# VIVA_PIC16_REV4-5.net
KiCad netlist of a schematic drawn in EAGLE
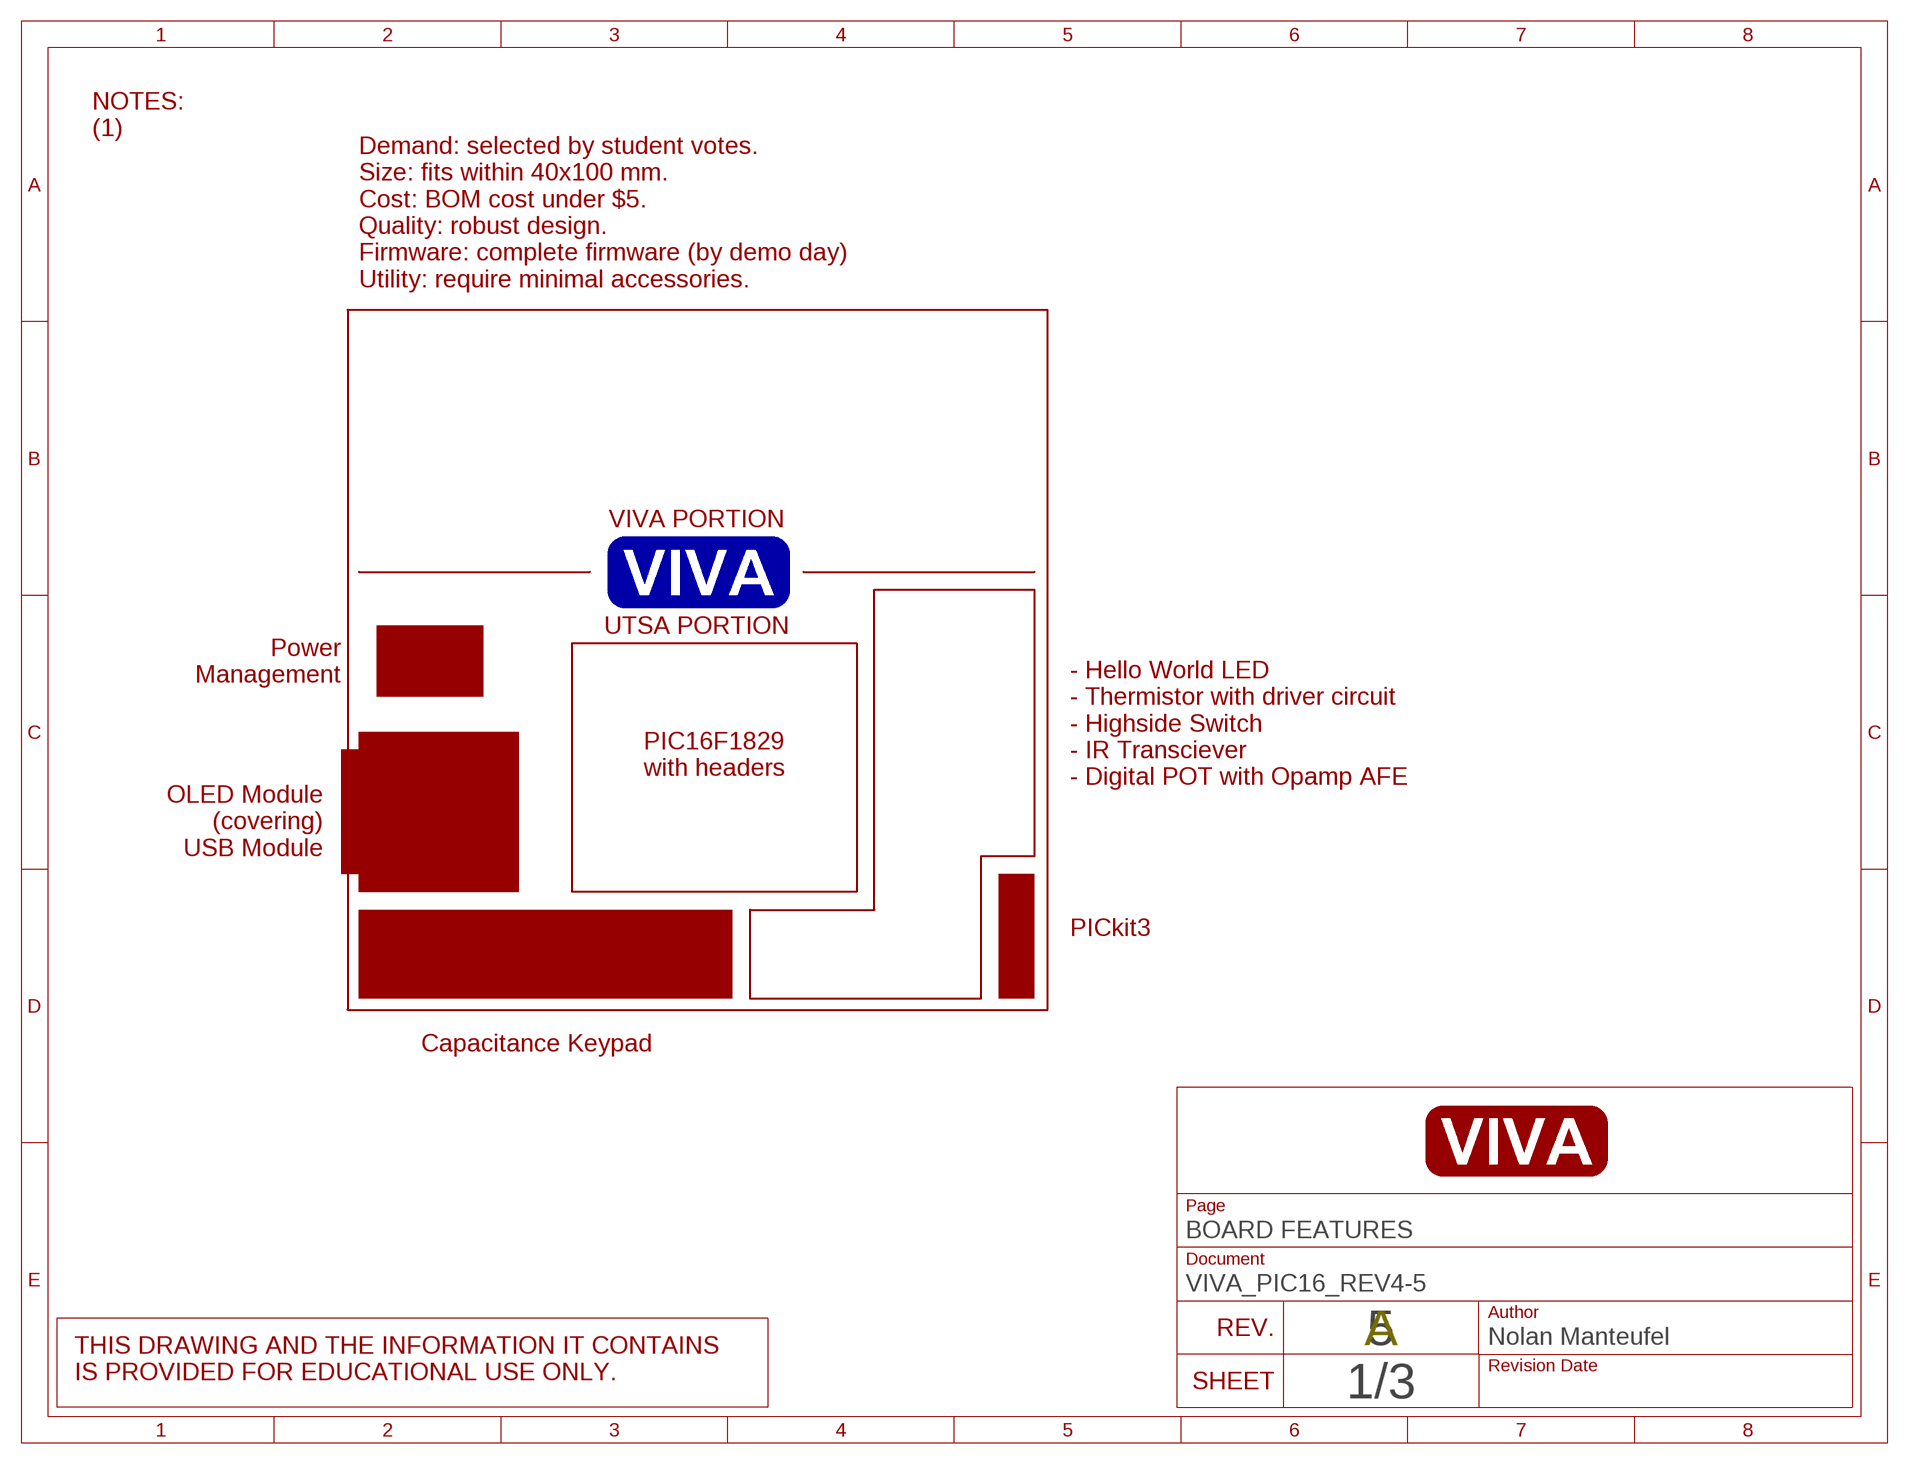
[diagram p0: schematic, sheet 1]
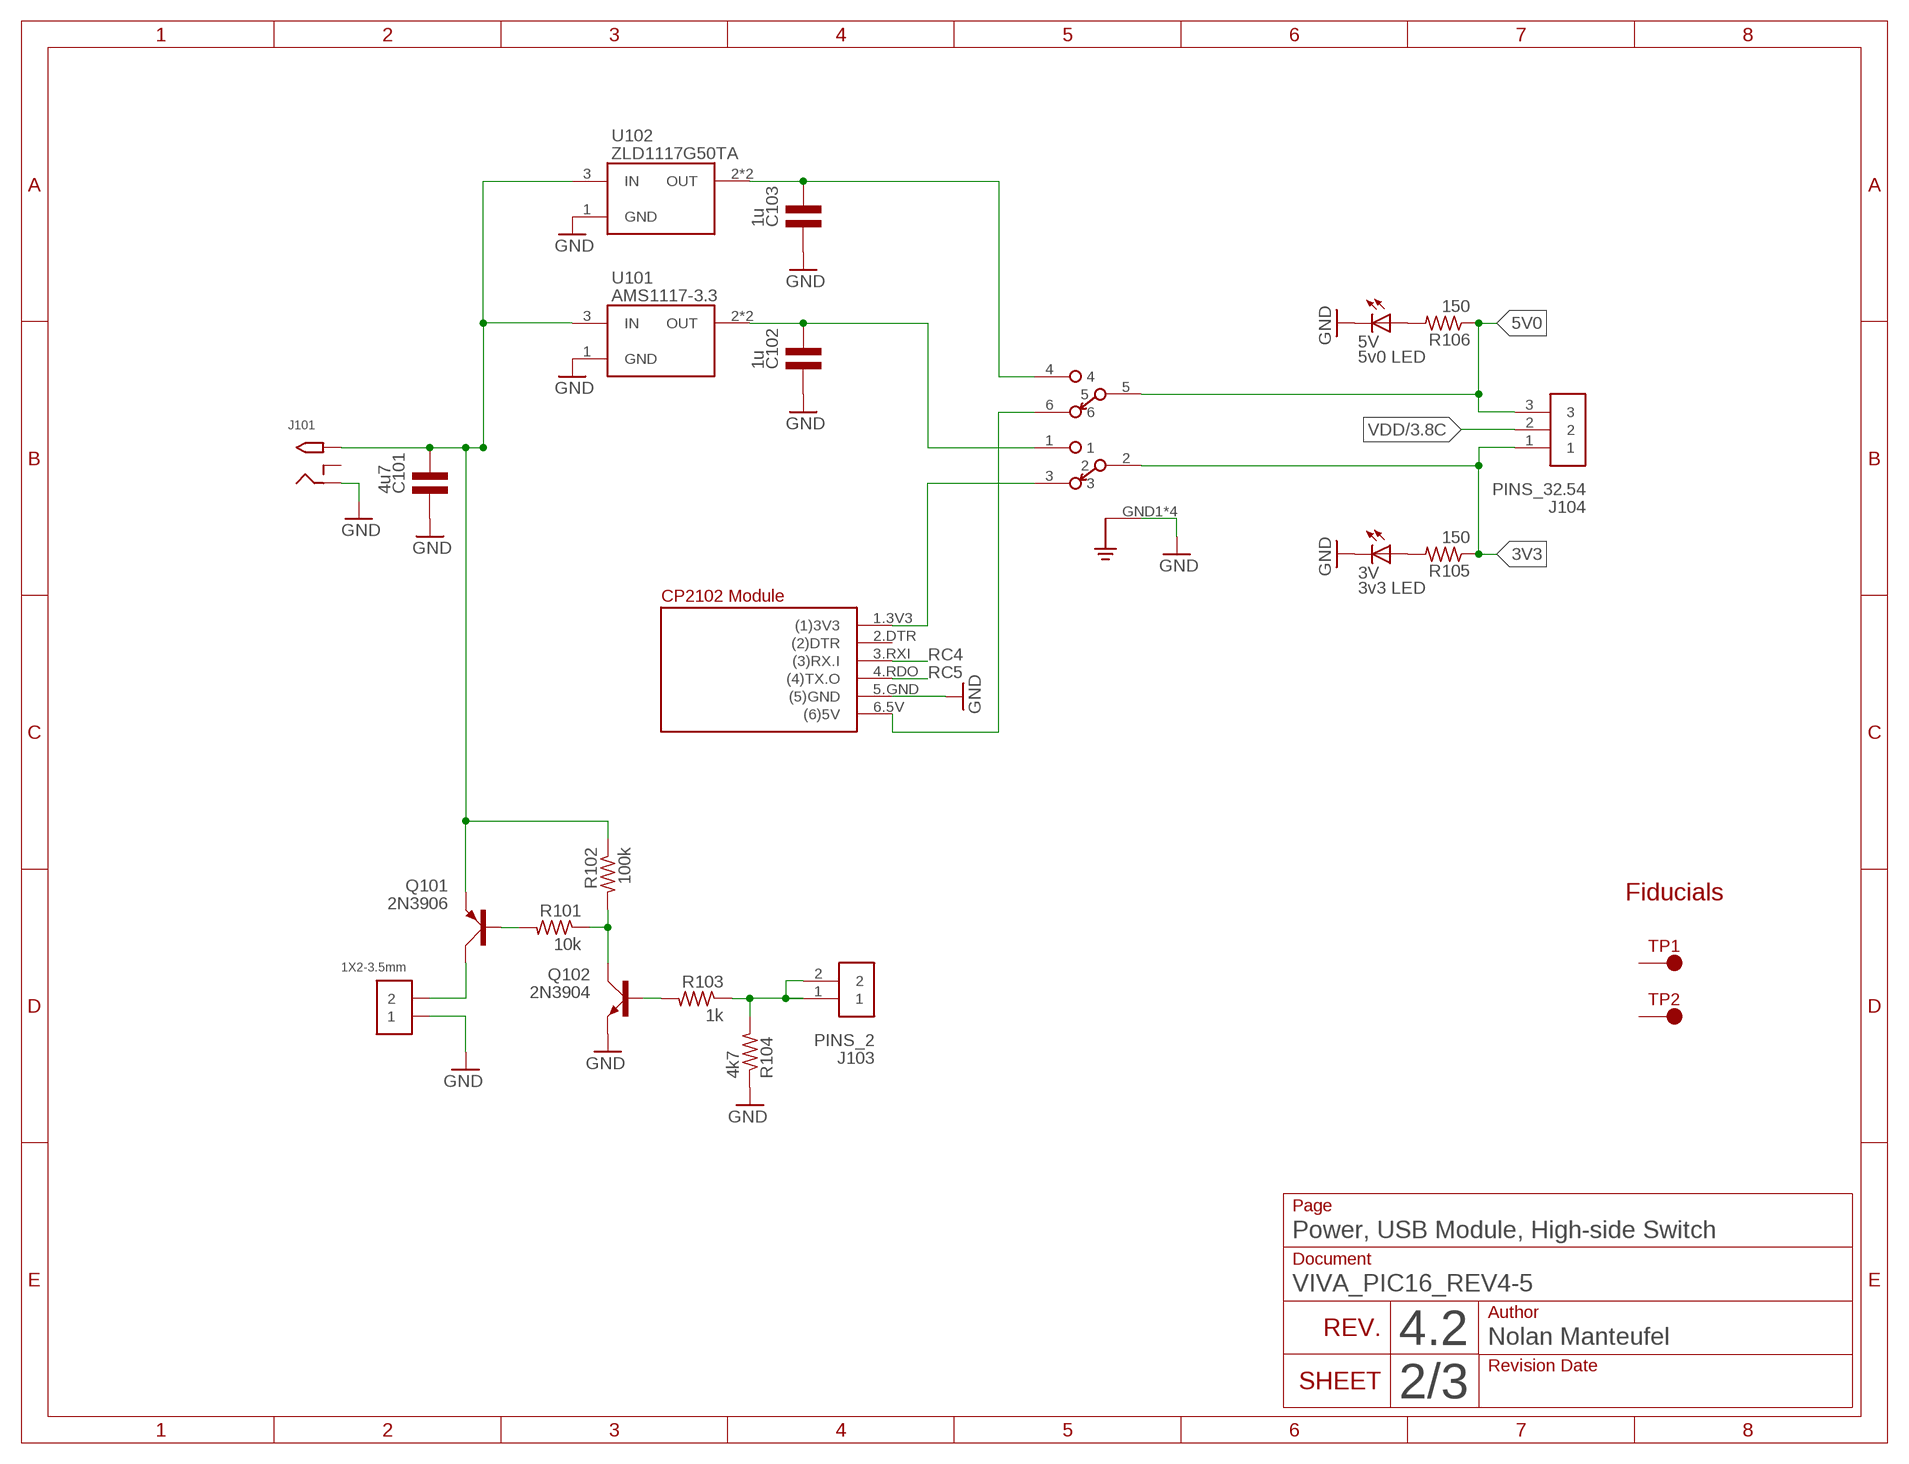
[diagram p1: schematic, sheet 2]
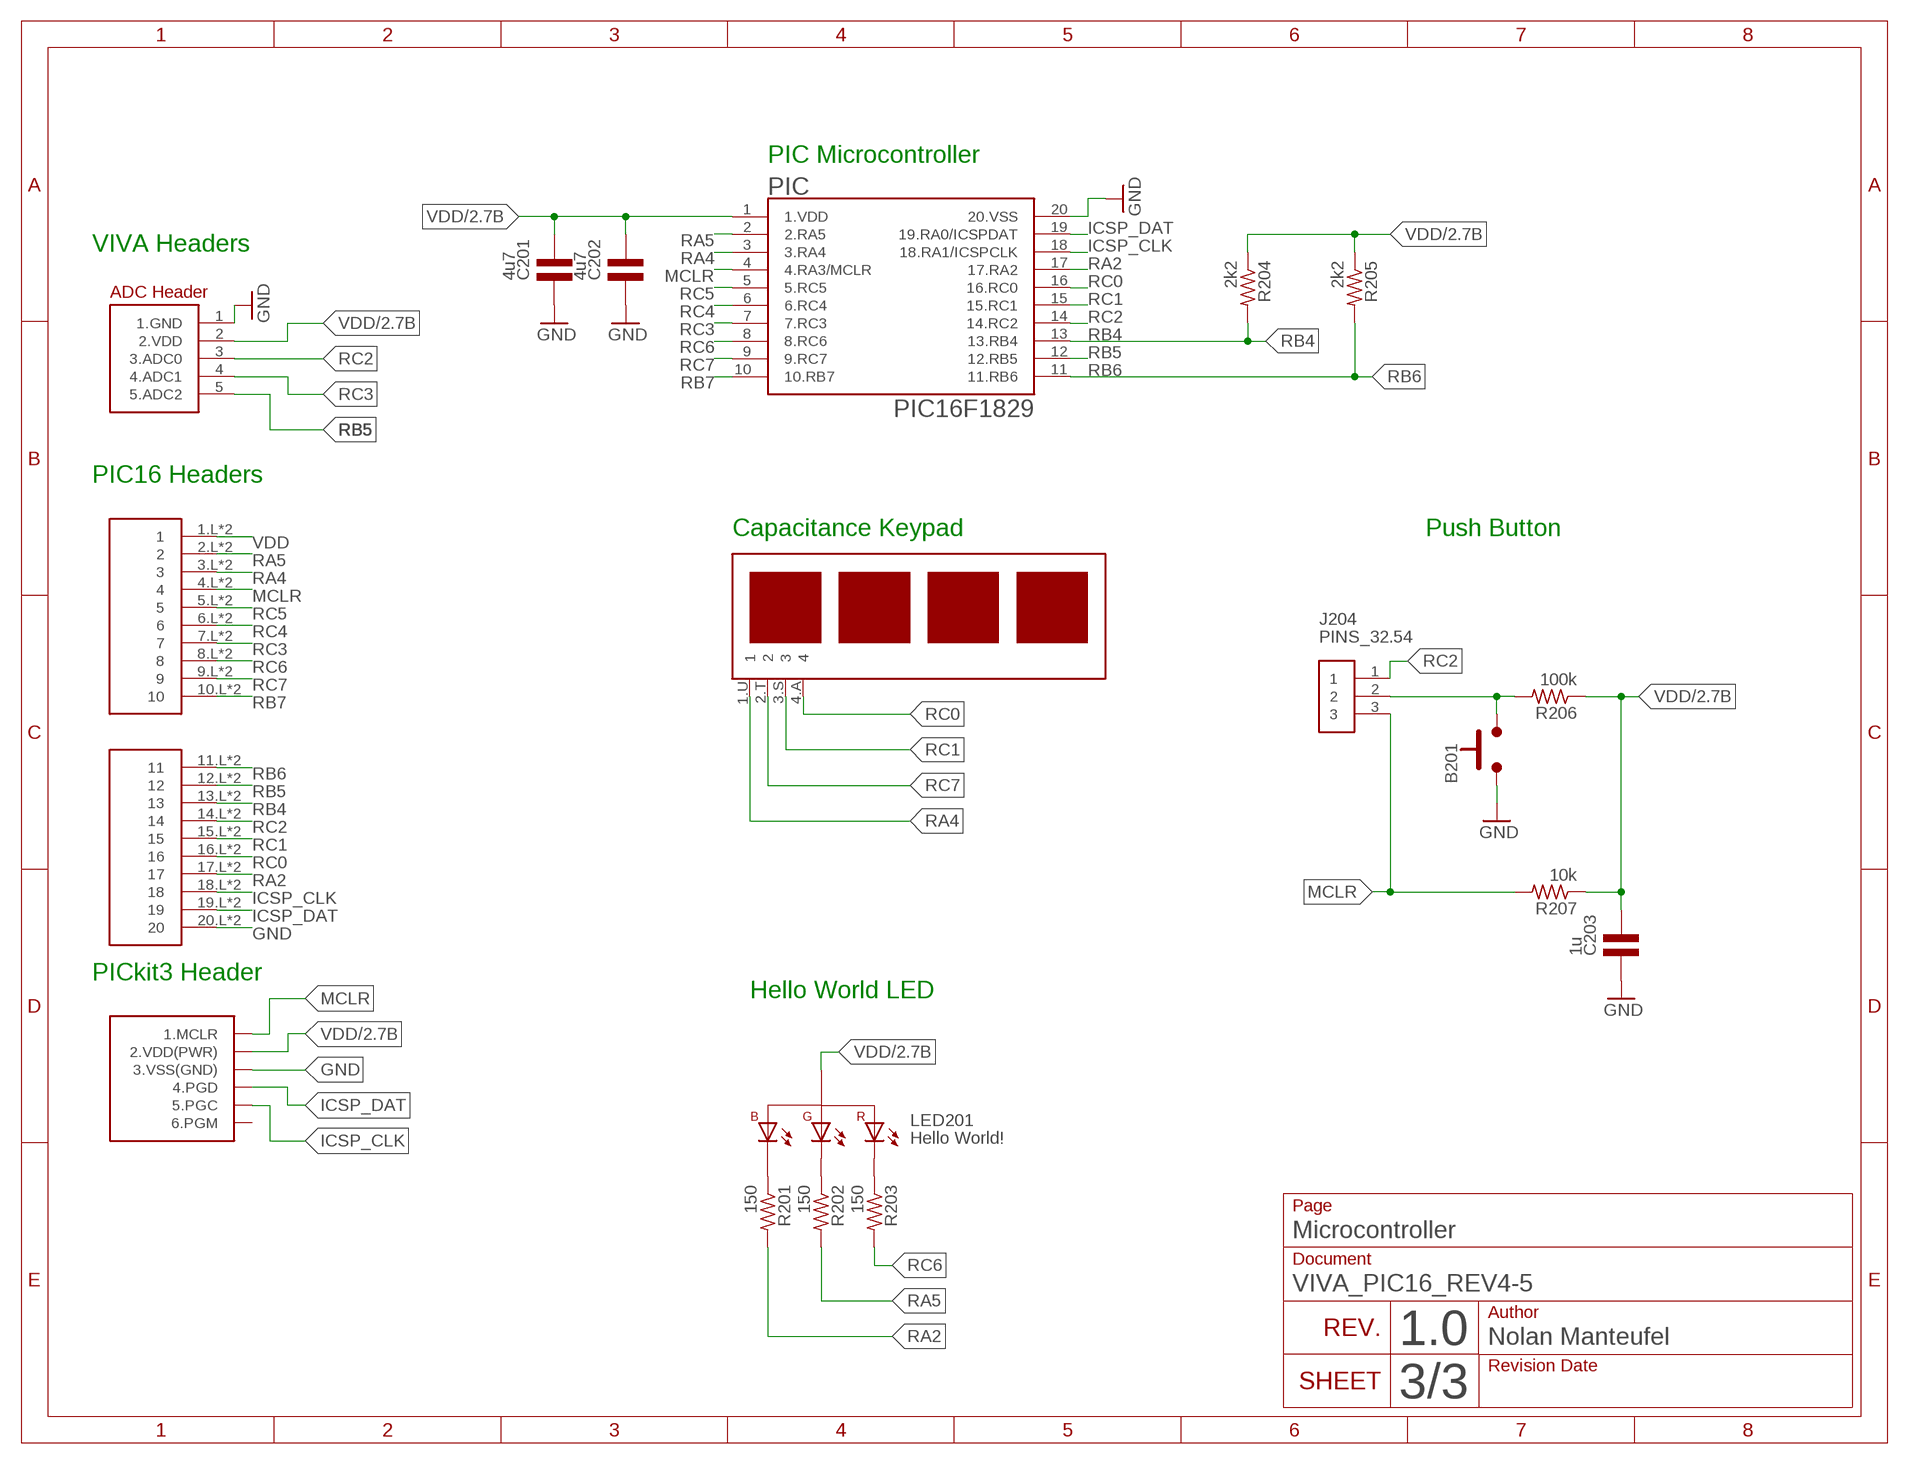
[diagram p2: schematic, sheet 3]

(export (version "E")
  (design (tool "Eeschema 10.0.6"))
  (components
    (comp (ref "B201")
      (value "PUSHBUTTON6X6MM")
      (footprint "eagle-import:6X6MM")
      (libsource (lib "eagle-import") (part "PUSHBUTTON6X6MM"))
    )
    (comp (ref "C201")
      (value "4u7")
      (footprint "eagle-import:C0805")
      (libsource (lib "eagle-import") (part "C0805"))
    )
    (comp (ref "C202")
      (value "4u7")
      (footprint "eagle-import:C0805")
      (libsource (lib "eagle-import") (part "C0805"))
    )
    (comp (ref "C203")
      (value "1u")
      (footprint "eagle-import:C0805")
      (libsource (lib "eagle-import") (part "C0805"))
    )
    (comp (ref "J201")
      (value "VIVA_PIC16")
      (footprint "eagle-import:VIVA_PIC16")
      (libsource (lib "eagle-import") (part "VIVA_PIC16"))
    )
    (comp (ref "J202")
      (value "VIVA-HEADER-ADCNONAME")
      (footprint "eagle-import:VIVA-HEADER-ADC-NONAME")
      (libsource (lib "eagle-import") (part "VIVA-HEADER-ADCNONAME"))
    )
    (comp (ref "J203")
      (value "PICKIT3")
      (footprint "eagle-import:PICKIT3")
      (libsource (lib "eagle-import") (part "PICKIT3"))
    )
    (comp (ref "J204")
      (value "PINS_32.54")
      (footprint "eagle-import:PINS_3")
      (libsource (lib "eagle-import") (part "PINS_32.54"))
    )
    (comp (ref "LED201")
      (value "Hello World!")
      (footprint "eagle-import:LED_RGB-5050")
      (libsource (lib "eagle-import") (part "RGB_LED"))
    )
    (comp (ref "PIC")
      (value "PIC16F1829")
      (footprint "eagle-import:SOP20-NEW")
      (libsource (lib "eagle-import") (part "PIC16F1829"))
    )
    (comp (ref "R201")
      (value "150")
      (footprint "eagle-import:R0805")
      (libsource (lib "eagle-import") (part "R-US_R0805"))
    )
    (comp (ref "R202")
      (value "150")
      (footprint "eagle-import:R0805")
      (libsource (lib "eagle-import") (part "R-US_R0805"))
    )
    (comp (ref "R203")
      (value "150")
      (footprint "eagle-import:R0805")
      (libsource (lib "eagle-import") (part "R-US_R0805"))
    )
    (comp (ref "R204")
      (value "2k2")
      (footprint "eagle-import:R0805")
      (libsource (lib "eagle-import") (part "R-US_R0805"))
    )
    (comp (ref "R205")
      (value "2k2")
      (footprint "eagle-import:R0805")
      (libsource (lib "eagle-import") (part "R-US_R0805"))
    )
    (comp (ref "R206")
      (value "100k")
      (footprint "eagle-import:R0805")
      (libsource (lib "eagle-import") (part "R-US_R0805"))
    )
    (comp (ref "R207")
      (value "10k")
      (footprint "eagle-import:R0805")
      (libsource (lib "eagle-import") (part "R-US_R0805"))
    )
    (comp (ref "U$201")
      (value "VIVA_UTSA-KEYPAD")
      (footprint "eagle-import:VIVA_UTSA-KEYPAD")
      (libsource (lib "eagle-import") (part "VIVA_UTSA-KEYPAD"))
    )
    (comp (ref "3V")
      (value "3v3 LED")
      (footprint "eagle-import:CHIPLED_0805")
      (libsource (lib "eagle-import") (part "LEDCHIPLED_0805"))
    )
    (comp (ref "5V")
      (value "5v0 LED")
      (footprint "eagle-import:CHIPLED_0805")
      (libsource (lib "eagle-import") (part "LEDCHIPLED_0805"))
    )
    (comp (ref "C101")
      (value "4u7")
      (footprint "eagle-import:C0805")
      (libsource (lib "eagle-import") (part "C0805"))
    )
    (comp (ref "C102")
      (value "1u")
      (footprint "eagle-import:C0805")
      (libsource (lib "eagle-import") (part "C0805"))
    )
    (comp (ref "C103")
      (value "1u")
      (footprint "eagle-import:C0805")
      (libsource (lib "eagle-import") (part "C0805"))
    )
    (comp (ref "J101")
      (value "2.1MMJACKTHM")
      (footprint "eagle-import:PJ-102A")
      (libsource (lib "eagle-import") (part "2.1MMJACKTHM"))
    )
    (comp (ref "J102")
      (value "1X2-3.5MM-3.5MM")
      (footprint "eagle-import:1X2-3.5MM")
      (libsource (lib "eagle-import") (part "1X2-3.5MM-3.5MM"))
    )
    (comp (ref "J103")
      (value "PINS_2")
      (footprint "eagle-import:PINS_2")
      (libsource (lib "eagle-import") (part "PINS_2"))
    )
    (comp (ref "J104")
      (value "PINS_32.54")
      (footprint "eagle-import:PINS_3")
      (libsource (lib "eagle-import") (part "PINS_32.54"))
    )
    (comp (ref "M101")
      (value "VIVA_USB-TTL")
      (footprint "eagle-import:VIVA_USB_TTL_SUBTEXT")
      (libsource (lib "eagle-import") (part "VIVA_USB-TTL"))
    )
    (comp (ref "Q101")
      (value "2N3906")
      (footprint "eagle-import:SOT23")
      (libsource (lib "eagle-import") (part "2N3906SOT23"))
    )
    (comp (ref "Q102")
      (value "2N3904")
      (footprint "eagle-import:SOT23")
      (libsource (lib "eagle-import") (part "2N3904SOT23"))
    )
    (comp (ref "R101")
      (value "10k")
      (footprint "eagle-import:R0805")
      (libsource (lib "eagle-import") (part "R-US_R0805"))
    )
    (comp (ref "R102")
      (value "100k")
      (footprint "eagle-import:R0805")
      (libsource (lib "eagle-import") (part "R-US_R0805"))
    )
    (comp (ref "R103")
      (value "1k")
      (footprint "eagle-import:R0805")
      (libsource (lib "eagle-import") (part "R-US_R0805"))
    )
    (comp (ref "R104")
      (value "4k7")
      (footprint "eagle-import:R0805")
      (libsource (lib "eagle-import") (part "R-US_R0805"))
    )
    (comp (ref "R105")
      (value "150")
      (footprint "eagle-import:R0805")
      (libsource (lib "eagle-import") (part "R-US_R0805"))
    )
    (comp (ref "R106")
      (value "150")
      (footprint "eagle-import:R0805")
      (libsource (lib "eagle-import") (part "R-US_R0805"))
    )
    (comp (ref "S101")
      (value "SWITCH_OS202013")
      (footprint "eagle-import:OS202013MT5QN1")
      (libsource (lib "eagle-import") (part "SWITCH_OS202013"))
    )
    (comp (ref "TP1")
      (value "TESTPOINTFIDUCIAL")
      (footprint "eagle-import:FIDUCIAL")
      (libsource (lib "eagle-import") (part "TESTPOINTFIDUCIAL"))
    )
    (comp (ref "TP2")
      (value "TESTPOINTFIDUCIAL")
      (footprint "eagle-import:FIDUCIAL")
      (libsource (lib "eagle-import") (part "TESTPOINTFIDUCIAL"))
    )
    (comp (ref "U101")
      (value "AMS1117-3.3")
      (footprint "eagle-import:SOT223")
      (libsource (lib "eagle-import") (part "REGULATOR_SCHLM1117"))
    )
    (comp (ref "U102")
      (value "ZLD1117G50TA")
      (footprint "eagle-import:SOT223")
      (libsource (lib "eagle-import") (part "REGULATOR_SCHLM1117"))
    )
    (comp (ref "U$1")
      (value "VIVA_LOGO")
      (footprint "eagle-import:VIVA_LOGO")
      (libsource (lib "eagle-import") (part "VIVA_LOGO"))
    )
  )
  (nets
    (net (code "1") (name "3V3") (class "Default")
      (node (ref "J104") (pin "1") (pinfunction "1_1") (pintype "bidirectional"))
      (node (ref "R105") (pin "1") (pinfunction "1_1") (pintype "passive"))
      (node (ref "S101") (pin "2") (pinfunction "2_2") (pintype "bidirectional"))
    )
    (net (code "2") (name "5V0") (class "Default")
      (node (ref "J104") (pin "3") (pinfunction "3_3") (pintype "bidirectional"))
      (node (ref "R106") (pin "1") (pinfunction "1_1") (pintype "passive"))
      (node (ref "S101") (pin "5") (pinfunction "5_5") (pintype "bidirectional"))
    )
    (net (code "3") (name "GND") (class "Default")
      (node (ref "3V") (pin "C") (pinfunction "C_C") (pintype "passive"))
      (node (ref "5V") (pin "C") (pinfunction "C_C") (pintype "passive"))
      (node (ref "B201") (pin "1.A") (pinfunction "1_1.A") (pintype "bidirectional"))
      (node (ref "B201") (pin "2.A") (pinfunction "1_2.A") (pintype "bidirectional"))
      (node (ref "C101") (pin "1") (pinfunction "P$1_1") (pintype "passive"))
      (node (ref "C102") (pin "1") (pinfunction "P$1_1") (pintype "passive"))
      (node (ref "C103") (pin "1") (pinfunction "P$1_1") (pintype "passive"))
      (node (ref "C201") (pin "1") (pinfunction "P$1_1") (pintype "passive"))
      (node (ref "C202") (pin "1") (pinfunction "P$1_1") (pintype "passive"))
      (node (ref "C203") (pin "1") (pinfunction "P$1_1") (pintype "passive"))
      (node (ref "J101") (pin "RING") (pinfunction "RING_RING") (pintype "bidirectional"))
      (node (ref "J102") (pin "1") (pinfunction "1_1") (pintype "passive"))
      (node (ref "J201") (pin "20.L") (pinfunction "20_20.L") (pintype "bidirectional"))
      (node (ref "J201") (pin "20.R") (pinfunction "20_20.R") (pintype "bidirectional"))
      (node (ref "J202") (pin "1") (pinfunction "1.GND_1") (pintype "bidirectional"))
      (node (ref "J203") (pin "3") (pinfunction "3.VSS(GND)_3") (pintype "bidirectional"))
      (node (ref "M101") (pin "5.GND") (pinfunction "(5)GND_5.GND") (pintype "bidirectional"))
      (node (ref "PIC") (pin "20") (pinfunction "20.VSS_20") (pintype "bidirectional"))
      (node (ref "Q102") (pin "2") (pinfunction "E_2") (pintype "passive"))
      (node (ref "R104") (pin "1") (pinfunction "1_1") (pintype "passive"))
      (node (ref "S101") (pin "GND1") (pinfunction "GND_GND1") (pintype "bidirectional"))
      (node (ref "S101") (pin "GND2") (pinfunction "GND_GND2") (pintype "bidirectional"))
      (node (ref "S101") (pin "GND3") (pinfunction "GND_GND3") (pintype "bidirectional"))
      (node (ref "S101") (pin "GND4") (pinfunction "GND_GND4") (pintype "bidirectional"))
      (node (ref "U101") (pin "1") (pinfunction "GND_1") (pintype "bidirectional"))
      (node (ref "U102") (pin "1") (pinfunction "GND_1") (pintype "bidirectional"))
    )
    (net (code "4") (name "ICSP_CLK") (class "Default")
      (node (ref "J201") (pin "18.L") (pinfunction "18_18.L") (pintype "bidirectional"))
      (node (ref "J201") (pin "18.R") (pinfunction "18_18.R") (pintype "bidirectional"))
      (node (ref "J203") (pin "5") (pinfunction "5.PGC_5") (pintype "bidirectional"))
      (node (ref "PIC") (pin "18") (pinfunction "18.RA1/ICSPCLK_18") (pintype "bidirectional"))
    )
    (net (code "5") (name "ICSP_DAT") (class "Default")
      (node (ref "J201") (pin "19.L") (pinfunction "19_19.L") (pintype "bidirectional"))
      (node (ref "J201") (pin "19.R") (pinfunction "19_19.R") (pintype "bidirectional"))
      (node (ref "J203") (pin "4") (pinfunction "4.PGD_4") (pintype "bidirectional"))
      (node (ref "PIC") (pin "19") (pinfunction "19.RA0/ICSPDAT_19") (pintype "bidirectional"))
    )
    (net (code "6") (name "MCLR") (class "Default")
      (node (ref "J201") (pin "4.L") (pinfunction "4_4.L") (pintype "bidirectional"))
      (node (ref "J201") (pin "4.R") (pinfunction "4_4.R") (pintype "bidirectional"))
      (node (ref "J203") (pin "1") (pinfunction "1.MCLR_1") (pintype "bidirectional"))
      (node (ref "J204") (pin "3") (pinfunction "3_3") (pintype "bidirectional"))
      (node (ref "PIC") (pin "4") (pinfunction "4.RA3/MCLR_4") (pintype "bidirectional"))
      (node (ref "R207") (pin "2") (pinfunction "2_2") (pintype "passive"))
    )
    (net (code "7") (name "Net-(3V-PadA)") (class "Default")
      (node (ref "3V") (pin "A") (pinfunction "A_A") (pintype "passive"))
      (node (ref "R105") (pin "2") (pinfunction "2_2") (pintype "passive"))
    )
    (net (code "8") (name "Net-(5V-PadA)") (class "Default")
      (node (ref "5V") (pin "A") (pinfunction "A_A") (pintype "passive"))
      (node (ref "R106") (pin "2") (pinfunction "2_2") (pintype "passive"))
    )
    (net (code "9") (name "Net-(B201-2-Pad3.B)") (class "Default")
      (node (ref "B201") (pin "3.B") (pinfunction "2_3.B") (pintype "bidirectional"))
      (node (ref "B201") (pin "4.B") (pinfunction "2_4.B") (pintype "bidirectional"))
      (node (ref "J204") (pin "2") (pinfunction "2_2") (pintype "bidirectional"))
      (node (ref "R206") (pin "2") (pinfunction "2_2") (pintype "passive"))
    )
    (net (code "10") (name "Net-(C101-P$2)") (class "Default")
      (node (ref "C101") (pin "2") (pinfunction "P$2_2") (pintype "passive"))
      (node (ref "J101") (pin "TIP") (pinfunction "TIP_TIP") (pintype "bidirectional"))
      (node (ref "Q101") (pin "2") (pinfunction "E_2") (pintype "passive"))
      (node (ref "R102") (pin "1") (pinfunction "1_1") (pintype "passive"))
      (node (ref "U101") (pin "3") (pinfunction "IN_3") (pintype "bidirectional"))
      (node (ref "U102") (pin "3") (pinfunction "IN_3") (pintype "bidirectional"))
    )
    (net (code "11") (name "Net-(C102-P$2)") (class "Default")
      (node (ref "C102") (pin "2") (pinfunction "P$2_2") (pintype "passive"))
      (node (ref "S101") (pin "1") (pinfunction "1_1") (pintype "bidirectional"))
      (node (ref "U101") (pin "2") (pinfunction "OUT_2") (pintype "bidirectional"))
      (node (ref "U101") (pin "4.TAB") (pinfunction "OUT_4.TAB") (pintype "bidirectional"))
    )
    (net (code "12") (name "Net-(C103-P$2)") (class "Default")
      (node (ref "C103") (pin "2") (pinfunction "P$2_2") (pintype "passive"))
      (node (ref "S101") (pin "4") (pinfunction "4_4") (pintype "bidirectional"))
      (node (ref "U102") (pin "2") (pinfunction "OUT_2") (pintype "bidirectional"))
      (node (ref "U102") (pin "4.TAB") (pinfunction "OUT_4.TAB") (pintype "bidirectional"))
    )
    (net (code "13") (name "Net-(J103-Pad1)") (class "Default")
      (node (ref "J103") (pin "1") (pinfunction "1_1") (pintype "bidirectional"))
      (node (ref "J103") (pin "2") (pinfunction "2_2") (pintype "bidirectional"))
      (node (ref "R103") (pin "1") (pinfunction "1_1") (pintype "passive"))
      (node (ref "R104") (pin "2") (pinfunction "2_2") (pintype "passive"))
    )
    (net (code "14") (name "Net-(LED201-Pad1.R-)") (class "Default")
      (node (ref "LED201") (pin "1.R-") (pinfunction "1.R-_1.R-") (pintype "passive"))
      (node (ref "R203") (pin "1") (pinfunction "1_1") (pintype "passive"))
    )
    (net (code "15") (name "Net-(LED201-Pad2.G-)") (class "Default")
      (node (ref "LED201") (pin "2.G-") (pinfunction "2.G-_2.G-") (pintype "passive"))
      (node (ref "R202") (pin "1") (pinfunction "1_1") (pintype "passive"))
    )
    (net (code "16") (name "Net-(LED201-Pad4.B-)") (class "Default")
      (node (ref "LED201") (pin "4.B-") (pinfunction "4.B-_4.B-") (pintype "passive"))
      (node (ref "R201") (pin "1") (pinfunction "1_1") (pintype "passive"))
    )
    (net (code "17") (name "Net-(M101-(1)3V3)") (class "Default")
      (node (ref "M101") (pin "1.3V3") (pinfunction "(1)3V3_1.3V3") (pintype "bidirectional"))
      (node (ref "S101") (pin "3") (pinfunction "3_3") (pintype "bidirectional"))
    )
    (net (code "18") (name "Net-(M101-(6)5V)") (class "Default")
      (node (ref "M101") (pin "6.5V") (pinfunction "(6)5V_6.5V") (pintype "bidirectional"))
      (node (ref "S101") (pin "6") (pinfunction "6_6") (pintype "bidirectional"))
    )
    (net (code "19") (name "Net-(Q101-B)") (class "Default")
      (node (ref "Q101") (pin "1") (pinfunction "B_1") (pintype "passive"))
      (node (ref "R101") (pin "2") (pinfunction "2_2") (pintype "passive"))
    )
    (net (code "20") (name "Net-(Q101-C)") (class "Default")
      (node (ref "J102") (pin "2") (pinfunction "2_2") (pintype "passive"))
      (node (ref "Q101") (pin "3") (pinfunction "C_3") (pintype "passive"))
    )
    (net (code "21") (name "Net-(Q102-B)") (class "Default")
      (node (ref "Q102") (pin "1") (pinfunction "B_1") (pintype "passive"))
      (node (ref "R103") (pin "2") (pinfunction "2_2") (pintype "passive"))
    )
    (net (code "22") (name "Net-(Q102-C)") (class "Default")
      (node (ref "Q102") (pin "3") (pinfunction "C_3") (pintype "passive"))
      (node (ref "R101") (pin "1") (pinfunction "1_1") (pintype "passive"))
      (node (ref "R102") (pin "2") (pinfunction "2_2") (pintype "passive"))
    )
    (net (code "23") (name "RA2") (class "Default")
      (node (ref "J201") (pin "17.L") (pinfunction "17_17.L") (pintype "bidirectional"))
      (node (ref "J201") (pin "17.R") (pinfunction "17_17.R") (pintype "bidirectional"))
      (node (ref "PIC") (pin "17") (pinfunction "17.RA2_17") (pintype "bidirectional"))
      (node (ref "R201") (pin "2") (pinfunction "2_2") (pintype "passive"))
    )
    (net (code "24") (name "RA4") (class "Default")
      (node (ref "J201") (pin "3.L") (pinfunction "3_3.L") (pintype "bidirectional"))
      (node (ref "J201") (pin "3.R") (pinfunction "3_3.R") (pintype "bidirectional"))
      (node (ref "PIC") (pin "3") (pinfunction "3.RA4_3") (pintype "bidirectional"))
      (node (ref "U$201") (pin "1.U") (pinfunction "1_1.U") (pintype "bidirectional"))
    )
    (net (code "25") (name "RA5") (class "Default")
      (node (ref "J201") (pin "2.L") (pinfunction "2_2.L") (pintype "bidirectional"))
      (node (ref "J201") (pin "2.R") (pinfunction "2_2.R") (pintype "bidirectional"))
      (node (ref "PIC") (pin "2") (pinfunction "2.RA5_2") (pintype "bidirectional"))
      (node (ref "R202") (pin "2") (pinfunction "2_2") (pintype "passive"))
    )
    (net (code "26") (name "RB4") (class "Default")
      (node (ref "J201") (pin "13.L") (pinfunction "13_13.L") (pintype "bidirectional"))
      (node (ref "J201") (pin "13.R") (pinfunction "13_13.R") (pintype "bidirectional"))
      (node (ref "PIC") (pin "13") (pinfunction "13.RB4_13") (pintype "bidirectional"))
      (node (ref "R204") (pin "2") (pinfunction "2_2") (pintype "passive"))
    )
    (net (code "27") (name "RB5") (class "Default")
      (node (ref "J201") (pin "12.L") (pinfunction "12_12.L") (pintype "bidirectional"))
      (node (ref "J201") (pin "12.R") (pinfunction "12_12.R") (pintype "bidirectional"))
      (node (ref "J202") (pin "5") (pinfunction "5.ADC2_5") (pintype "bidirectional"))
      (node (ref "PIC") (pin "12") (pinfunction "12.RB5_12") (pintype "bidirectional"))
    )
    (net (code "28") (name "RB6") (class "Default")
      (node (ref "J201") (pin "11.L") (pinfunction "11_11.L") (pintype "bidirectional"))
      (node (ref "J201") (pin "11.R") (pinfunction "11_11.R") (pintype "bidirectional"))
      (node (ref "PIC") (pin "11") (pinfunction "11.RB6_11") (pintype "bidirectional"))
      (node (ref "R205") (pin "2") (pinfunction "2_2") (pintype "passive"))
    )
    (net (code "29") (name "RB7") (class "Default")
      (node (ref "J201") (pin "10.L") (pinfunction "10_10.L") (pintype "bidirectional"))
      (node (ref "J201") (pin "10.R") (pinfunction "10_10.R") (pintype "bidirectional"))
      (node (ref "PIC") (pin "10") (pinfunction "10.RB7_10") (pintype "bidirectional"))
    )
    (net (code "30") (name "RC0") (class "Default")
      (node (ref "J201") (pin "16.L") (pinfunction "16_16.L") (pintype "bidirectional"))
      (node (ref "J201") (pin "16.R") (pinfunction "16_16.R") (pintype "bidirectional"))
      (node (ref "PIC") (pin "16") (pinfunction "16.RC0_16") (pintype "bidirectional"))
      (node (ref "U$201") (pin "4.A") (pinfunction "4_4.A") (pintype "bidirectional"))
    )
    (net (code "31") (name "RC1") (class "Default")
      (node (ref "J201") (pin "15.L") (pinfunction "15_15.L") (pintype "bidirectional"))
      (node (ref "J201") (pin "15.R") (pinfunction "15_15.R") (pintype "bidirectional"))
      (node (ref "PIC") (pin "15") (pinfunction "15.RC1_15") (pintype "bidirectional"))
      (node (ref "U$201") (pin "3.S") (pinfunction "3_3.S") (pintype "bidirectional"))
    )
    (net (code "32") (name "RC2") (class "Default")
      (node (ref "J201") (pin "14.L") (pinfunction "14_14.L") (pintype "bidirectional"))
      (node (ref "J201") (pin "14.R") (pinfunction "14_14.R") (pintype "bidirectional"))
      (node (ref "J202") (pin "3") (pinfunction "3.ADC0_3") (pintype "bidirectional"))
      (node (ref "J204") (pin "1") (pinfunction "1_1") (pintype "bidirectional"))
      (node (ref "PIC") (pin "14") (pinfunction "14.RC2_14") (pintype "bidirectional"))
    )
    (net (code "33") (name "RC3") (class "Default")
      (node (ref "J201") (pin "7.L") (pinfunction "7_7.L") (pintype "bidirectional"))
      (node (ref "J201") (pin "7.R") (pinfunction "7_7.R") (pintype "bidirectional"))
      (node (ref "J202") (pin "4") (pinfunction "4.ADC1_4") (pintype "bidirectional"))
      (node (ref "PIC") (pin "7") (pinfunction "7.RC3_7") (pintype "bidirectional"))
    )
    (net (code "34") (name "RC4") (class "Default")
      (node (ref "J201") (pin "6.L") (pinfunction "6_6.L") (pintype "bidirectional"))
      (node (ref "J201") (pin "6.R") (pinfunction "6_6.R") (pintype "bidirectional"))
      (node (ref "M101") (pin "3.RXI") (pinfunction "(3)RX.I_3.RXI") (pintype "bidirectional"))
      (node (ref "PIC") (pin "6") (pinfunction "6.RC4_6") (pintype "bidirectional"))
    )
    (net (code "35") (name "RC5") (class "Default")
      (node (ref "J201") (pin "5.L") (pinfunction "5_5.L") (pintype "bidirectional"))
      (node (ref "J201") (pin "5.R") (pinfunction "5_5.R") (pintype "bidirectional"))
      (node (ref "M101") (pin "4.RDO") (pinfunction "(4)TX.O_4.RDO") (pintype "bidirectional"))
      (node (ref "PIC") (pin "5") (pinfunction "5.RC5_5") (pintype "bidirectional"))
    )
    (net (code "36") (name "RC6") (class "Default")
      (node (ref "J201") (pin "8.L") (pinfunction "8_8.L") (pintype "bidirectional"))
      (node (ref "J201") (pin "8.R") (pinfunction "8_8.R") (pintype "bidirectional"))
      (node (ref "PIC") (pin "8") (pinfunction "8.RC6_8") (pintype "bidirectional"))
      (node (ref "R203") (pin "2") (pinfunction "2_2") (pintype "passive"))
    )
    (net (code "37") (name "RC7") (class "Default")
      (node (ref "J201") (pin "9.L") (pinfunction "9_9.L") (pintype "bidirectional"))
      (node (ref "J201") (pin "9.R") (pinfunction "9_9.R") (pintype "bidirectional"))
      (node (ref "PIC") (pin "9") (pinfunction "9.RC7_9") (pintype "bidirectional"))
      (node (ref "U$201") (pin "2.T") (pinfunction "2_2.T") (pintype "bidirectional"))
    )
    (net (code "38") (name "VDD") (class "Default")
      (node (ref "C201") (pin "2") (pinfunction "P$2_2") (pintype "passive"))
      (node (ref "C202") (pin "2") (pinfunction "P$2_2") (pintype "passive"))
      (node (ref "C203") (pin "2") (pinfunction "P$2_2") (pintype "passive"))
      (node (ref "J104") (pin "2") (pinfunction "2_2") (pintype "bidirectional"))
      (node (ref "J201") (pin "1.L") (pinfunction "1_1.L") (pintype "bidirectional"))
      (node (ref "J201") (pin "1.R") (pinfunction "1_1.R") (pintype "bidirectional"))
      (node (ref "J202") (pin "2") (pinfunction "2.VDD_2") (pintype "bidirectional"))
      (node (ref "J203") (pin "2") (pinfunction "2.VDD(PWR)_2") (pintype "bidirectional"))
      (node (ref "LED201") (pin "3.+") (pinfunction "3.+_3.+") (pintype "passive"))
      (node (ref "PIC") (pin "1") (pinfunction "1.VDD_1") (pintype "bidirectional"))
      (node (ref "R204") (pin "1") (pinfunction "1_1") (pintype "passive"))
      (node (ref "R205") (pin "1") (pinfunction "1_1") (pintype "passive"))
      (node (ref "R206") (pin "1") (pinfunction "1_1") (pintype "passive"))
      (node (ref "R207") (pin "1") (pinfunction "1_1") (pintype "passive"))
    )
    (net (code "39") (name "unconnected-(J101-PadRING_SW)") (class "Default")
      (node (ref "J101") (pin "RING_SW") (pinfunction "RING_SW_RING_SW") (pintype "bidirectional"))
    )
    (net (code "40") (name "unconnected-(J203-6.PGM-Pad6)") (class "Default")
      (node (ref "J203") (pin "6") (pinfunction "6.PGM_6") (pintype "bidirectional"))
    )
    (net (code "41") (name "unconnected-(M101-(2)DTR-Pad2.DTR)") (class "Default")
      (node (ref "M101") (pin "2.DTR") (pinfunction "(2)DTR_2.DTR") (pintype "bidirectional"))
    )
    (net (code "42") (name "unconnected-(TP1-P$1-PadFIDUCIAL)") (class "Default")
      (node (ref "TP1") (pin "FIDUCIAL") (pinfunction "P$1_FIDUCIAL") (pintype "bidirectional"))
    )
    (net (code "43") (name "unconnected-(TP2-P$1-PadFIDUCIAL)") (class "Default")
      (node (ref "TP2") (pin "FIDUCIAL") (pinfunction "P$1_FIDUCIAL") (pintype "bidirectional"))
    )
  )
)
